# d200_zm1020_rev_b.net
KiCad netlist of a schematic drawn in EAGLE
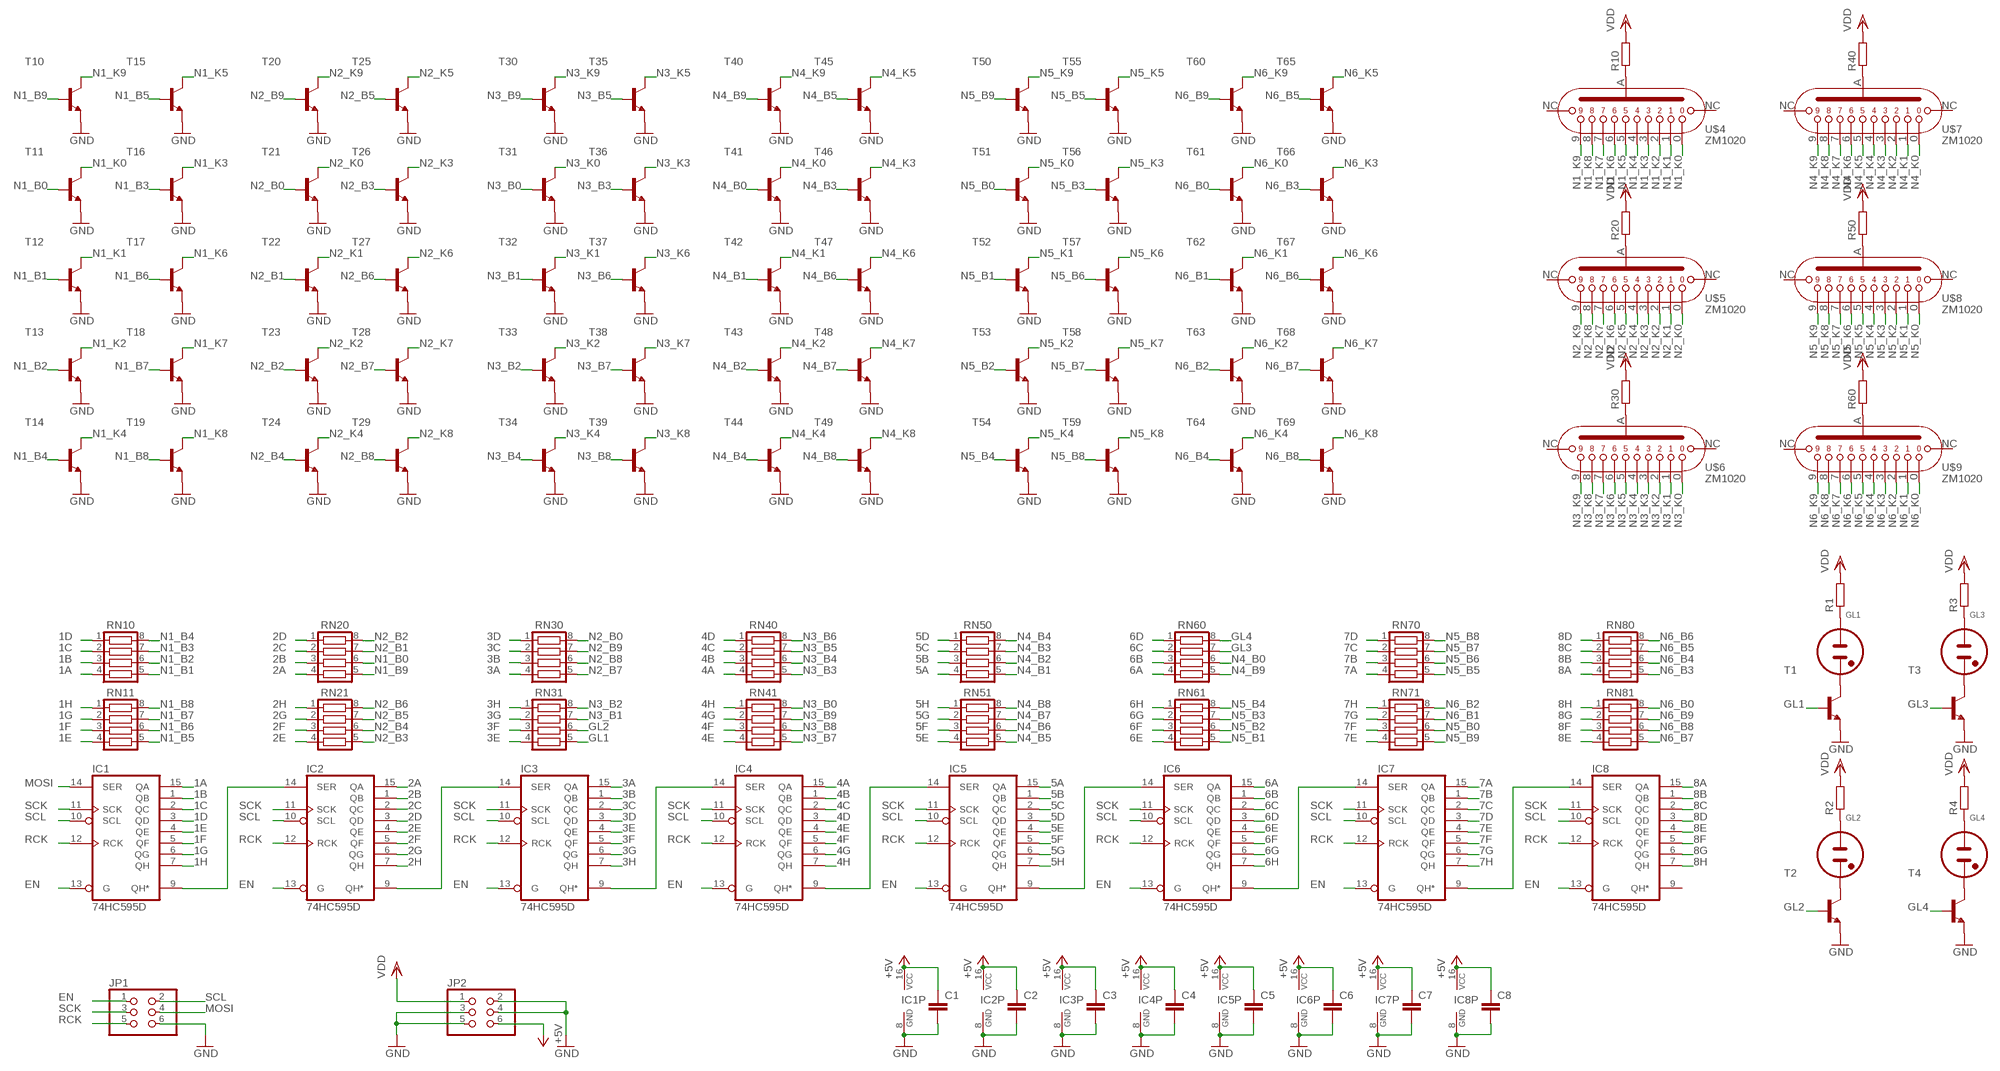
[diagram p0: schematic, sheet 1]

(export (version "E")
  (design (tool "Eeschema 10.0.6"))
  (components
    (comp (ref "C1")
      (value "C-EUC0603")
      (footprint "eagle-import:C0603")
      (libsource (lib "eagle-import") (part "C-EUC0603"))
    )
    (comp (ref "C2")
      (value "C-EUC0603")
      (footprint "eagle-import:C0603")
      (libsource (lib "eagle-import") (part "C-EUC0603"))
    )
    (comp (ref "C3")
      (value "C-EUC0603")
      (footprint "eagle-import:C0603")
      (libsource (lib "eagle-import") (part "C-EUC0603"))
    )
    (comp (ref "C4")
      (value "C-EUC0603")
      (footprint "eagle-import:C0603")
      (libsource (lib "eagle-import") (part "C-EUC0603"))
    )
    (comp (ref "C5")
      (value "C-EUC0603")
      (footprint "eagle-import:C0603")
      (libsource (lib "eagle-import") (part "C-EUC0603"))
    )
    (comp (ref "C6")
      (value "C-EUC0603")
      (footprint "eagle-import:C0603")
      (libsource (lib "eagle-import") (part "C-EUC0603"))
    )
    (comp (ref "C7")
      (value "C-EUC0603")
      (footprint "eagle-import:C0603")
      (libsource (lib "eagle-import") (part "C-EUC0603"))
    )
    (comp (ref "C8")
      (value "C-EUC0603")
      (footprint "eagle-import:C0603")
      (libsource (lib "eagle-import") (part "C-EUC0603"))
    )
    (comp (ref "GL1")
      (value "NE2-NEON-BULB-DRILL")
      (footprint "eagle-import:NE2-NEON-BULB-DRILL")
      (libsource (lib "eagle-import") (part "NE2-NEON-BULB-DRILL"))
    )
    (comp (ref "GL2")
      (value "NE2-NEON-BULB-DRILL")
      (footprint "eagle-import:NE2-NEON-BULB-DRILL")
      (libsource (lib "eagle-import") (part "NE2-NEON-BULB-DRILL"))
    )
    (comp (ref "GL3")
      (value "NE2-NEON-BULB-DRILL")
      (footprint "eagle-import:NE2-NEON-BULB-DRILL")
      (libsource (lib "eagle-import") (part "NE2-NEON-BULB-DRILL"))
    )
    (comp (ref "GL4")
      (value "NE2-NEON-BULB-DRILL")
      (footprint "eagle-import:NE2-NEON-BULB-DRILL")
      (libsource (lib "eagle-import") (part "NE2-NEON-BULB-DRILL"))
    )
    (comp (ref "IC1")
      (value "74HC595D")
      (footprint "eagle-import:SO16")
      (libsource (lib "eagle-import") (part "74595DHC"))
    )
    (comp (ref "IC2")
      (value "74HC595D")
      (footprint "eagle-import:SO16")
      (libsource (lib "eagle-import") (part "74595DHC"))
    )
    (comp (ref "IC3")
      (value "74HC595D")
      (footprint "eagle-import:SO16")
      (libsource (lib "eagle-import") (part "74595DHC"))
    )
    (comp (ref "IC4")
      (value "74HC595D")
      (footprint "eagle-import:SO16")
      (libsource (lib "eagle-import") (part "74595DHC"))
    )
    (comp (ref "IC5")
      (value "74HC595D")
      (footprint "eagle-import:SO16")
      (libsource (lib "eagle-import") (part "74595DHC"))
    )
    (comp (ref "IC6")
      (value "74HC595D")
      (footprint "eagle-import:SO16")
      (libsource (lib "eagle-import") (part "74595DHC"))
    )
    (comp (ref "IC7")
      (value "74HC595D")
      (footprint "eagle-import:SO16")
      (libsource (lib "eagle-import") (part "74595DHC"))
    )
    (comp (ref "IC8")
      (value "74HC595D")
      (footprint "eagle-import:SO16")
      (libsource (lib "eagle-import") (part "74595DHC"))
    )
    (comp (ref "JP1")
      (value "PINHD-2X3_2.54-SMD")
      (footprint "eagle-import:2X03SMD")
      (libsource (lib "eagle-import") (part "PINHD-2X3_2.54-SMD"))
    )
    (comp (ref "JP2")
      (value "PINHD-2X3_2.54-SMD")
      (footprint "eagle-import:2X03SMD")
      (libsource (lib "eagle-import") (part "PINHD-2X3_2.54-SMD"))
    )
    (comp (ref "R1")
      (value "R-EU_R0603")
      (footprint "eagle-import:R0603")
      (libsource (lib "eagle-import") (part "R-EU_R0603"))
    )
    (comp (ref "R2")
      (value "R-EU_R0603")
      (footprint "eagle-import:R0603")
      (libsource (lib "eagle-import") (part "R-EU_R0603"))
    )
    (comp (ref "R3")
      (value "R-EU_R0603")
      (footprint "eagle-import:R0603")
      (libsource (lib "eagle-import") (part "R-EU_R0603"))
    )
    (comp (ref "R4")
      (value "R-EU_R0603")
      (footprint "eagle-import:R0603")
      (libsource (lib "eagle-import") (part "R-EU_R0603"))
    )
    (comp (ref "R10")
      (value "R-EU_R0603")
      (footprint "eagle-import:R0603")
      (libsource (lib "eagle-import") (part "R-EU_R0603"))
    )
    (comp (ref "R20")
      (value "R-EU_R0603")
      (footprint "eagle-import:R0603")
      (libsource (lib "eagle-import") (part "R-EU_R0603"))
    )
    (comp (ref "R30")
      (value "R-EU_R0603")
      (footprint "eagle-import:R0603")
      (libsource (lib "eagle-import") (part "R-EU_R0603"))
    )
    (comp (ref "R40")
      (value "R-EU_R0603")
      (footprint "eagle-import:R0603")
      (libsource (lib "eagle-import") (part "R-EU_R0603"))
    )
    (comp (ref "R50")
      (value "R-EU_R0603")
      (footprint "eagle-import:R0603")
      (libsource (lib "eagle-import") (part "R-EU_R0603"))
    )
    (comp (ref "R60")
      (value "R-EU_R0603")
      (footprint "eagle-import:R0603")
      (libsource (lib "eagle-import") (part "R-EU_R0603"))
    )
    (comp (ref "RN10")
      (value "CTS742C083")
      (footprint "eagle-import:CTS742C083")
      (fields (field (name "OC_FARNELL") "unknown") (field (name "OC_NEWARK") "unknown"))
      (libsource (lib "eagle-import") (part "CTS742C083"))
    )
    (comp (ref "RN11")
      (value "CTS742C083")
      (footprint "eagle-import:CTS742C083")
      (fields (field (name "OC_FARNELL") "unknown") (field (name "OC_NEWARK") "unknown"))
      (libsource (lib "eagle-import") (part "CTS742C083"))
    )
    (comp (ref "RN20")
      (value "CTS742C083")
      (footprint "eagle-import:CTS742C083")
      (fields (field (name "OC_FARNELL") "unknown") (field (name "OC_NEWARK") "unknown"))
      (libsource (lib "eagle-import") (part "CTS742C083"))
    )
    (comp (ref "RN21")
      (value "CTS742C083")
      (footprint "eagle-import:CTS742C083")
      (fields (field (name "OC_FARNELL") "unknown") (field (name "OC_NEWARK") "unknown"))
      (libsource (lib "eagle-import") (part "CTS742C083"))
    )
    (comp (ref "RN30")
      (value "CTS742C083")
      (footprint "eagle-import:CTS742C083")
      (fields (field (name "OC_FARNELL") "unknown") (field (name "OC_NEWARK") "unknown"))
      (libsource (lib "eagle-import") (part "CTS742C083"))
    )
    (comp (ref "RN31")
      (value "CTS742C083")
      (footprint "eagle-import:CTS742C083")
      (fields (field (name "OC_FARNELL") "unknown") (field (name "OC_NEWARK") "unknown"))
      (libsource (lib "eagle-import") (part "CTS742C083"))
    )
    (comp (ref "RN40")
      (value "CTS742C083")
      (footprint "eagle-import:CTS742C083")
      (fields (field (name "OC_FARNELL") "unknown") (field (name "OC_NEWARK") "unknown"))
      (libsource (lib "eagle-import") (part "CTS742C083"))
    )
    (comp (ref "RN41")
      (value "CTS742C083")
      (footprint "eagle-import:CTS742C083")
      (fields (field (name "OC_FARNELL") "unknown") (field (name "OC_NEWARK") "unknown"))
      (libsource (lib "eagle-import") (part "CTS742C083"))
    )
    (comp (ref "RN50")
      (value "CTS742C083")
      (footprint "eagle-import:CTS742C083")
      (fields (field (name "OC_FARNELL") "unknown") (field (name "OC_NEWARK") "unknown"))
      (libsource (lib "eagle-import") (part "CTS742C083"))
    )
    (comp (ref "RN51")
      (value "CTS742C083")
      (footprint "eagle-import:CTS742C083")
      (fields (field (name "OC_FARNELL") "unknown") (field (name "OC_NEWARK") "unknown"))
      (libsource (lib "eagle-import") (part "CTS742C083"))
    )
    (comp (ref "RN60")
      (value "CTS742C083")
      (footprint "eagle-import:CTS742C083")
      (fields (field (name "OC_FARNELL") "unknown") (field (name "OC_NEWARK") "unknown"))
      (libsource (lib "eagle-import") (part "CTS742C083"))
    )
    (comp (ref "RN61")
      (value "CTS742C083")
      (footprint "eagle-import:CTS742C083")
      (fields (field (name "OC_FARNELL") "unknown") (field (name "OC_NEWARK") "unknown"))
      (libsource (lib "eagle-import") (part "CTS742C083"))
    )
    (comp (ref "RN70")
      (value "CTS742C083")
      (footprint "eagle-import:CTS742C083")
      (fields (field (name "OC_FARNELL") "unknown") (field (name "OC_NEWARK") "unknown"))
      (libsource (lib "eagle-import") (part "CTS742C083"))
    )
    (comp (ref "RN71")
      (value "CTS742C083")
      (footprint "eagle-import:CTS742C083")
      (fields (field (name "OC_FARNELL") "unknown") (field (name "OC_NEWARK") "unknown"))
      (libsource (lib "eagle-import") (part "CTS742C083"))
    )
    (comp (ref "RN80")
      (value "CTS742C083")
      (footprint "eagle-import:CTS742C083")
      (fields (field (name "OC_FARNELL") "unknown") (field (name "OC_NEWARK") "unknown"))
      (libsource (lib "eagle-import") (part "CTS742C083"))
    )
    (comp (ref "RN81")
      (value "CTS742C083")
      (footprint "eagle-import:CTS742C083")
      (fields (field (name "OC_FARNELL") "unknown") (field (name "OC_NEWARK") "unknown"))
      (libsource (lib "eagle-import") (part "CTS742C083"))
    )
    (comp (ref "T1")
      (value "SMBTA42")
      (footprint "eagle-import:SOT23")
      (libsource (lib "eagle-import") (part "SMBTA42"))
    )
    (comp (ref "T2")
      (value "SMBTA42")
      (footprint "eagle-import:SOT23")
      (libsource (lib "eagle-import") (part "SMBTA42"))
    )
    (comp (ref "T3")
      (value "SMBTA42")
      (footprint "eagle-import:SOT23")
      (libsource (lib "eagle-import") (part "SMBTA42"))
    )
    (comp (ref "T4")
      (value "SMBTA42")
      (footprint "eagle-import:SOT23")
      (libsource (lib "eagle-import") (part "SMBTA42"))
    )
    (comp (ref "T10")
      (value "SMBTA42")
      (footprint "eagle-import:SOT23")
      (libsource (lib "eagle-import") (part "SMBTA42"))
    )
    (comp (ref "T11")
      (value "SMBTA42")
      (footprint "eagle-import:SOT23")
      (libsource (lib "eagle-import") (part "SMBTA42"))
    )
    (comp (ref "T12")
      (value "SMBTA42")
      (footprint "eagle-import:SOT23")
      (libsource (lib "eagle-import") (part "SMBTA42"))
    )
    (comp (ref "T13")
      (value "SMBTA42")
      (footprint "eagle-import:SOT23")
      (libsource (lib "eagle-import") (part "SMBTA42"))
    )
    (comp (ref "T14")
      (value "SMBTA42")
      (footprint "eagle-import:SOT23")
      (libsource (lib "eagle-import") (part "SMBTA42"))
    )
    (comp (ref "T15")
      (value "SMBTA42")
      (footprint "eagle-import:SOT23")
      (libsource (lib "eagle-import") (part "SMBTA42"))
    )
    (comp (ref "T16")
      (value "SMBTA42")
      (footprint "eagle-import:SOT23")
      (libsource (lib "eagle-import") (part "SMBTA42"))
    )
    (comp (ref "T17")
      (value "SMBTA42")
      (footprint "eagle-import:SOT23")
      (libsource (lib "eagle-import") (part "SMBTA42"))
    )
    (comp (ref "T18")
      (value "SMBTA42")
      (footprint "eagle-import:SOT23")
      (libsource (lib "eagle-import") (part "SMBTA42"))
    )
    (comp (ref "T19")
      (value "SMBTA42")
      (footprint "eagle-import:SOT23")
      (libsource (lib "eagle-import") (part "SMBTA42"))
    )
    (comp (ref "T20")
      (value "SMBTA42")
      (footprint "eagle-import:SOT23")
      (libsource (lib "eagle-import") (part "SMBTA42"))
    )
    (comp (ref "T21")
      (value "SMBTA42")
      (footprint "eagle-import:SOT23")
      (libsource (lib "eagle-import") (part "SMBTA42"))
    )
    (comp (ref "T22")
      (value "SMBTA42")
      (footprint "eagle-import:SOT23")
      (libsource (lib "eagle-import") (part "SMBTA42"))
    )
    (comp (ref "T23")
      (value "SMBTA42")
      (footprint "eagle-import:SOT23")
      (libsource (lib "eagle-import") (part "SMBTA42"))
    )
    (comp (ref "T24")
      (value "SMBTA42")
      (footprint "eagle-import:SOT23")
      (libsource (lib "eagle-import") (part "SMBTA42"))
    )
    (comp (ref "T25")
      (value "SMBTA42")
      (footprint "eagle-import:SOT23")
      (libsource (lib "eagle-import") (part "SMBTA42"))
    )
    (comp (ref "T26")
      (value "SMBTA42")
      (footprint "eagle-import:SOT23")
      (libsource (lib "eagle-import") (part "SMBTA42"))
    )
    (comp (ref "T27")
      (value "SMBTA42")
      (footprint "eagle-import:SOT23")
      (libsource (lib "eagle-import") (part "SMBTA42"))
    )
    (comp (ref "T28")
      (value "SMBTA42")
      (footprint "eagle-import:SOT23")
      (libsource (lib "eagle-import") (part "SMBTA42"))
    )
    (comp (ref "T29")
      (value "SMBTA42")
      (footprint "eagle-import:SOT23")
      (libsource (lib "eagle-import") (part "SMBTA42"))
    )
    (comp (ref "T30")
      (value "SMBTA42")
      (footprint "eagle-import:SOT23")
      (libsource (lib "eagle-import") (part "SMBTA42"))
    )
    (comp (ref "T31")
      (value "SMBTA42")
      (footprint "eagle-import:SOT23")
      (libsource (lib "eagle-import") (part "SMBTA42"))
    )
    (comp (ref "T32")
      (value "SMBTA42")
      (footprint "eagle-import:SOT23")
      (libsource (lib "eagle-import") (part "SMBTA42"))
    )
    (comp (ref "T33")
      (value "SMBTA42")
      (footprint "eagle-import:SOT23")
      (libsource (lib "eagle-import") (part "SMBTA42"))
    )
    (comp (ref "T34")
      (value "SMBTA42")
      (footprint "eagle-import:SOT23")
      (libsource (lib "eagle-import") (part "SMBTA42"))
    )
    (comp (ref "T35")
      (value "SMBTA42")
      (footprint "eagle-import:SOT23")
      (libsource (lib "eagle-import") (part "SMBTA42"))
    )
    (comp (ref "T36")
      (value "SMBTA42")
      (footprint "eagle-import:SOT23")
      (libsource (lib "eagle-import") (part "SMBTA42"))
    )
    (comp (ref "T37")
      (value "SMBTA42")
      (footprint "eagle-import:SOT23")
      (libsource (lib "eagle-import") (part "SMBTA42"))
    )
    (comp (ref "T38")
      (value "SMBTA42")
      (footprint "eagle-import:SOT23")
      (libsource (lib "eagle-import") (part "SMBTA42"))
    )
    (comp (ref "T39")
      (value "SMBTA42")
      (footprint "eagle-import:SOT23")
      (libsource (lib "eagle-import") (part "SMBTA42"))
    )
    (comp (ref "T40")
      (value "SMBTA42")
      (footprint "eagle-import:SOT23")
      (libsource (lib "eagle-import") (part "SMBTA42"))
    )
    (comp (ref "T41")
      (value "SMBTA42")
      (footprint "eagle-import:SOT23")
      (libsource (lib "eagle-import") (part "SMBTA42"))
    )
    (comp (ref "T42")
      (value "SMBTA42")
      (footprint "eagle-import:SOT23")
      (libsource (lib "eagle-import") (part "SMBTA42"))
    )
    (comp (ref "T43")
      (value "SMBTA42")
      (footprint "eagle-import:SOT23")
      (libsource (lib "eagle-import") (part "SMBTA42"))
    )
    (comp (ref "T44")
      (value "SMBTA42")
      (footprint "eagle-import:SOT23")
      (libsource (lib "eagle-import") (part "SMBTA42"))
    )
    (comp (ref "T45")
      (value "SMBTA42")
      (footprint "eagle-import:SOT23")
      (libsource (lib "eagle-import") (part "SMBTA42"))
    )
    (comp (ref "T46")
      (value "SMBTA42")
      (footprint "eagle-import:SOT23")
      (libsource (lib "eagle-import") (part "SMBTA42"))
    )
    (comp (ref "T47")
      (value "SMBTA42")
      (footprint "eagle-import:SOT23")
      (libsource (lib "eagle-import") (part "SMBTA42"))
    )
    (comp (ref "T48")
      (value "SMBTA42")
      (footprint "eagle-import:SOT23")
      (libsource (lib "eagle-import") (part "SMBTA42"))
    )
    (comp (ref "T49")
      (value "SMBTA42")
      (footprint "eagle-import:SOT23")
      (libsource (lib "eagle-import") (part "SMBTA42"))
    )
    (comp (ref "T50")
      (value "SMBTA42")
      (footprint "eagle-import:SOT23")
      (libsource (lib "eagle-import") (part "SMBTA42"))
    )
    (comp (ref "T51")
      (value "SMBTA42")
      (footprint "eagle-import:SOT23")
      (libsource (lib "eagle-import") (part "SMBTA42"))
    )
    (comp (ref "T52")
      (value "SMBTA42")
      (footprint "eagle-import:SOT23")
      (libsource (lib "eagle-import") (part "SMBTA42"))
    )
    (comp (ref "T53")
      (value "SMBTA42")
      (footprint "eagle-import:SOT23")
      (libsource (lib "eagle-import") (part "SMBTA42"))
    )
    (comp (ref "T54")
      (value "SMBTA42")
      (footprint "eagle-import:SOT23")
      (libsource (lib "eagle-import") (part "SMBTA42"))
    )
    (comp (ref "T55")
      (value "SMBTA42")
      (footprint "eagle-import:SOT23")
      (libsource (lib "eagle-import") (part "SMBTA42"))
    )
    (comp (ref "T56")
      (value "SMBTA42")
      (footprint "eagle-import:SOT23")
      (libsource (lib "eagle-import") (part "SMBTA42"))
    )
    (comp (ref "T57")
      (value "SMBTA42")
      (footprint "eagle-import:SOT23")
      (libsource (lib "eagle-import") (part "SMBTA42"))
    )
    (comp (ref "T58")
      (value "SMBTA42")
      (footprint "eagle-import:SOT23")
      (libsource (lib "eagle-import") (part "SMBTA42"))
    )
    (comp (ref "T59")
      (value "SMBTA42")
      (footprint "eagle-import:SOT23")
      (libsource (lib "eagle-import") (part "SMBTA42"))
    )
    (comp (ref "T60")
      (value "SMBTA42")
      (footprint "eagle-import:SOT23")
      (libsource (lib "eagle-import") (part "SMBTA42"))
    )
    (comp (ref "T61")
      (value "SMBTA42")
      (footprint "eagle-import:SOT23")
      (libsource (lib "eagle-import") (part "SMBTA42"))
    )
    (comp (ref "T62")
      (value "SMBTA42")
      (footprint "eagle-import:SOT23")
      (libsource (lib "eagle-import") (part "SMBTA42"))
    )
    (comp (ref "T63")
      (value "SMBTA42")
      (footprint "eagle-import:SOT23")
      (libsource (lib "eagle-import") (part "SMBTA42"))
    )
    (comp (ref "T64")
      (value "SMBTA42")
      (footprint "eagle-import:SOT23")
      (libsource (lib "eagle-import") (part "SMBTA42"))
    )
    (comp (ref "T65")
      (value "SMBTA42")
      (footprint "eagle-import:SOT23")
      (libsource (lib "eagle-import") (part "SMBTA42"))
    )
    (comp (ref "T66")
      (value "SMBTA42")
      (footprint "eagle-import:SOT23")
      (libsource (lib "eagle-import") (part "SMBTA42"))
    )
    (comp (ref "T67")
      (value "SMBTA42")
      (footprint "eagle-import:SOT23")
      (libsource (lib "eagle-import") (part "SMBTA42"))
    )
    (comp (ref "T68")
      (value "SMBTA42")
      (footprint "eagle-import:SOT23")
      (libsource (lib "eagle-import") (part "SMBTA42"))
    )
    (comp (ref "T69")
      (value "SMBTA42")
      (footprint "eagle-import:SOT23")
      (libsource (lib "eagle-import") (part "SMBTA42"))
    )
    (comp (ref "U$4")
      (value "ZM1020")
      (footprint "eagle-import:ZM1020")
      (libsource (lib "eagle-import") (part "ZM1020"))
    )
    (comp (ref "U$5")
      (value "ZM1020")
      (footprint "eagle-import:ZM1020")
      (libsource (lib "eagle-import") (part "ZM1020"))
    )
    (comp (ref "U$6")
      (value "ZM1020")
      (footprint "eagle-import:ZM1020")
      (libsource (lib "eagle-import") (part "ZM1020"))
    )
    (comp (ref "U$7")
      (value "ZM1020")
      (footprint "eagle-import:ZM1020")
      (libsource (lib "eagle-import") (part "ZM1020"))
    )
    (comp (ref "U$8")
      (value "ZM1020")
      (footprint "eagle-import:ZM1020")
      (libsource (lib "eagle-import") (part "ZM1020"))
    )
    (comp (ref "U$9")
      (value "ZM1020")
      (footprint "eagle-import:ZM1020")
      (libsource (lib "eagle-import") (part "ZM1020"))
    )
  )
  (nets
    (net (code "1") (name "+5V") (class "Default")
      (node (ref "C1") (pin "1") (pinfunction "1_1") (pintype "passive"))
      (node (ref "C2") (pin "1") (pinfunction "1_1") (pintype "passive"))
      (node (ref "C3") (pin "1") (pinfunction "1_1") (pintype "passive"))
      (node (ref "C4") (pin "1") (pinfunction "1_1") (pintype "passive"))
      (node (ref "C5") (pin "1") (pinfunction "1_1") (pintype "passive"))
      (node (ref "C6") (pin "1") (pinfunction "1_1") (pintype "passive"))
      (node (ref "C7") (pin "1") (pinfunction "1_1") (pintype "passive"))
      (node (ref "C8") (pin "1") (pinfunction "1_1") (pintype "passive"))
      (node (ref "IC1") (pin "16") (pinfunction "VCC_16") (pintype "power_in"))
      (node (ref "IC2") (pin "16") (pinfunction "VCC_16") (pintype "power_in"))
      (node (ref "IC3") (pin "16") (pinfunction "VCC_16") (pintype "power_in"))
      (node (ref "IC4") (pin "16") (pinfunction "VCC_16") (pintype "power_in"))
      (node (ref "IC5") (pin "16") (pinfunction "VCC_16") (pintype "power_in"))
      (node (ref "IC6") (pin "16") (pinfunction "VCC_16") (pintype "power_in"))
      (node (ref "IC7") (pin "16") (pinfunction "VCC_16") (pintype "power_in"))
      (node (ref "IC8") (pin "16") (pinfunction "VCC_16") (pintype "power_in"))
      (node (ref "JP2") (pin "6") (pinfunction "6_6") (pintype "passive"))
    )
    (net (code "2") (name "/1A") (class "Default")
      (node (ref "IC1") (pin "15") (pinfunction "QA_15") (pintype "tri_state"))
      (node (ref "RN10") (pin "4") (pinfunction "4_4") (pintype "passive"))
    )
    (net (code "3") (name "/1B") (class "Default")
      (node (ref "IC1") (pin "1") (pinfunction "QB_1") (pintype "tri_state"))
      (node (ref "RN10") (pin "3") (pinfunction "3_3") (pintype "passive"))
    )
    (net (code "4") (name "/1C") (class "Default")
      (node (ref "IC1") (pin "2") (pinfunction "QC_2") (pintype "tri_state"))
      (node (ref "RN10") (pin "2") (pinfunction "2_2") (pintype "passive"))
    )
    (net (code "5") (name "/1D") (class "Default")
      (node (ref "IC1") (pin "3") (pinfunction "QD_3") (pintype "tri_state"))
      (node (ref "RN10") (pin "1") (pinfunction "1_1") (pintype "passive"))
    )
    (net (code "6") (name "/1E") (class "Default")
      (node (ref "IC1") (pin "4") (pinfunction "QE_4") (pintype "tri_state"))
      (node (ref "RN11") (pin "4") (pinfunction "4_4") (pintype "passive"))
    )
    (net (code "7") (name "/1F") (class "Default")
      (node (ref "IC1") (pin "5") (pinfunction "QF_5") (pintype "tri_state"))
      (node (ref "RN11") (pin "3") (pinfunction "3_3") (pintype "passive"))
    )
    (net (code "8") (name "/1G") (class "Default")
      (node (ref "IC1") (pin "6") (pinfunction "QG_6") (pintype "tri_state"))
      (node (ref "RN11") (pin "2") (pinfunction "2_2") (pintype "passive"))
    )
    (net (code "9") (name "/1H") (class "Default")
      (node (ref "IC1") (pin "7") (pinfunction "QH_7") (pintype "tri_state"))
      (node (ref "RN11") (pin "1") (pinfunction "1_1") (pintype "passive"))
    )
    (net (code "10") (name "/2A") (class "Default")
      (node (ref "IC2") (pin "15") (pinfunction "QA_15") (pintype "tri_state"))
      (node (ref "RN20") (pin "4") (pinfunction "4_4") (pintype "passive"))
    )
    (net (code "11") (name "/2B") (class "Default")
      (node (ref "IC2") (pin "1") (pinfunction "QB_1") (pintype "tri_state"))
      (node (ref "RN20") (pin "3") (pinfunction "3_3") (pintype "passive"))
    )
    (net (code "12") (name "/2C") (class "Default")
      (node (ref "IC2") (pin "2") (pinfunction "QC_2") (pintype "tri_state"))
      (node (ref "RN20") (pin "2") (pinfunction "2_2") (pintype "passive"))
    )
    (net (code "13") (name "/2D") (class "Default")
      (node (ref "IC2") (pin "3") (pinfunction "QD_3") (pintype "tri_state"))
      (node (ref "RN20") (pin "1") (pinfunction "1_1") (pintype "passive"))
    )
    (net (code "14") (name "/2E") (class "Default")
      (node (ref "IC2") (pin "4") (pinfunction "QE_4") (pintype "tri_state"))
      (node (ref "RN21") (pin "4") (pinfunction "4_4") (pintype "passive"))
    )
    (net (code "15") (name "/2F") (class "Default")
      (node (ref "IC2") (pin "5") (pinfunction "QF_5") (pintype "tri_state"))
      (node (ref "RN21") (pin "3") (pinfunction "3_3") (pintype "passive"))
    )
    (net (code "16") (name "/2G") (class "Default")
      (node (ref "IC2") (pin "6") (pinfunction "QG_6") (pintype "tri_state"))
      (node (ref "RN21") (pin "2") (pinfunction "2_2") (pintype "passive"))
    )
    (net (code "17") (name "/2H") (class "Default")
      (node (ref "IC2") (pin "7") (pinfunction "QH_7") (pintype "tri_state"))
      (node (ref "RN21") (pin "1") (pinfunction "1_1") (pintype "passive"))
    )
    (net (code "18") (name "/3A") (class "Default")
      (node (ref "IC3") (pin "15") (pinfunction "QA_15") (pintype "tri_state"))
      (node (ref "RN30") (pin "4") (pinfunction "4_4") (pintype "passive"))
    )
    (net (code "19") (name "/3B") (class "Default")
      (node (ref "IC3") (pin "1") (pinfunction "QB_1") (pintype "tri_state"))
      (node (ref "RN30") (pin "3") (pinfunction "3_3") (pintype "passive"))
    )
    (net (code "20") (name "/3C") (class "Default")
      (node (ref "IC3") (pin "2") (pinfunction "QC_2") (pintype "tri_state"))
      (node (ref "RN30") (pin "2") (pinfunction "2_2") (pintype "passive"))
    )
    (net (code "21") (name "/3D") (class "Default")
      (node (ref "IC3") (pin "3") (pinfunction "QD_3") (pintype "tri_state"))
      (node (ref "RN30") (pin "1") (pinfunction "1_1") (pintype "passive"))
    )
    (net (code "22") (name "/3E") (class "Default")
      (node (ref "IC3") (pin "4") (pinfunction "QE_4") (pintype "tri_state"))
      (node (ref "RN31") (pin "4") (pinfunction "4_4") (pintype "passive"))
    )
    (net (code "23") (name "/3F") (class "Default")
      (node (ref "IC3") (pin "5") (pinfunction "QF_5") (pintype "tri_state"))
      (node (ref "RN31") (pin "3") (pinfunction "3_3") (pintype "passive"))
    )
    (net (code "24") (name "/3G") (class "Default")
      (node (ref "IC3") (pin "6") (pinfunction "QG_6") (pintype "tri_state"))
      (node (ref "RN31") (pin "2") (pinfunction "2_2") (pintype "passive"))
    )
    (net (code "25") (name "/3H") (class "Default")
      (node (ref "IC3") (pin "7") (pinfunction "QH_7") (pintype "tri_state"))
      (node (ref "RN31") (pin "1") (pinfunction "1_1") (pintype "passive"))
    )
    (net (code "26") (name "/4A") (class "Default")
      (node (ref "IC4") (pin "15") (pinfunction "QA_15") (pintype "tri_state"))
      (node (ref "RN40") (pin "4") (pinfunction "4_4") (pintype "passive"))
    )
    (net (code "27") (name "/4B") (class "Default")
      (node (ref "IC4") (pin "1") (pinfunction "QB_1") (pintype "tri_state"))
      (node (ref "RN40") (pin "3") (pinfunction "3_3") (pintype "passive"))
    )
    (net (code "28") (name "/4C") (class "Default")
      (node (ref "IC4") (pin "2") (pinfunction "QC_2") (pintype "tri_state"))
      (node (ref "RN40") (pin "2") (pinfunction "2_2") (pintype "passive"))
    )
    (net (code "29") (name "/4D") (class "Default")
      (node (ref "IC4") (pin "3") (pinfunction "QD_3") (pintype "tri_state"))
      (node (ref "RN40") (pin "1") (pinfunction "1_1") (pintype "passive"))
    )
    (net (code "30") (name "/4E") (class "Default")
      (node (ref "IC4") (pin "4") (pinfunction "QE_4") (pintype "tri_state"))
      (node (ref "RN41") (pin "4") (pinfunction "4_4") (pintype "passive"))
    )
    (net (code "31") (name "/4F") (class "Default")
      (node (ref "IC4") (pin "5") (pinfunction "QF_5") (pintype "tri_state"))
      (node (ref "RN41") (pin "3") (pinfunction "3_3") (pintype "passive"))
    )
    (net (code "32") (name "/4G") (class "Default")
      (node (ref "IC4") (pin "6") (pinfunction "QG_6") (pintype "tri_state"))
      (node (ref "RN41") (pin "2") (pinfunction "2_2") (pintype "passive"))
    )
    (net (code "33") (name "/4H") (class "Default")
      (node (ref "IC4") (pin "7") (pinfunction "QH_7") (pintype "tri_state"))
      (node (ref "RN41") (pin "1") (pinfunction "1_1") (pintype "passive"))
    )
    (net (code "34") (name "/5A") (class "Default")
      (node (ref "IC5") (pin "15") (pinfunction "QA_15") (pintype "tri_state"))
      (node (ref "RN50") (pin "4") (pinfunction "4_4") (pintype "passive"))
    )
    (net (code "35") (name "/5B") (class "Default")
      (node (ref "IC5") (pin "1") (pinfunction "QB_1") (pintype "tri_state"))
      (node (ref "RN50") (pin "3") (pinfunction "3_3") (pintype "passive"))
    )
    (net (code "36") (name "/5C") (class "Default")
      (node (ref "IC5") (pin "2") (pinfunction "QC_2") (pintype "tri_state"))
      (node (ref "RN50") (pin "2") (pinfunction "2_2") (pintype "passive"))
    )
    (net (code "37") (name "/5D") (class "Default")
      (node (ref "IC5") (pin "3") (pinfunction "QD_3") (pintype "tri_state"))
      (node (ref "RN50") (pin "1") (pinfunction "1_1") (pintype "passive"))
    )
    (net (code "38") (name "/5E") (class "Default")
      (node (ref "IC5") (pin "4") (pinfunction "QE_4") (pintype "tri_state"))
      (node (ref "RN51") (pin "4") (pinfunction "4_4") (pintype "passive"))
    )
    (net (code "39") (name "/5F") (class "Default")
      (node (ref "IC5") (pin "5") (pinfunction "QF_5") (pintype "tri_state"))
      (node (ref "RN51") (pin "3") (pinfunction "3_3") (pintype "passive"))
    )
    (net (code "40") (name "/5G") (class "Default")
      (node (ref "IC5") (pin "6") (pinfunction "QG_6") (pintype "tri_state"))
      (node (ref "RN51") (pin "2") (pinfunction "2_2") (pintype "passive"))
    )
    (net (code "41") (name "/5H") (class "Default")
      (node (ref "IC5") (pin "7") (pinfunction "QH_7") (pintype "tri_state"))
      (node (ref "RN51") (pin "1") (pinfunction "1_1") (pintype "passive"))
    )
    (net (code "42") (name "/6A") (class "Default")
      (node (ref "IC6") (pin "15") (pinfunction "QA_15") (pintype "tri_state"))
      (node (ref "RN60") (pin "4") (pinfunction "4_4") (pintype "passive"))
    )
    (net (code "43") (name "/6B") (class "Default")
      (node (ref "IC6") (pin "1") (pinfunction "QB_1") (pintype "tri_state"))
      (node (ref "RN60") (pin "3") (pinfunction "3_3") (pintype "passive"))
    )
    (net (code "44") (name "/6C") (class "Default")
      (node (ref "IC6") (pin "2") (pinfunction "QC_2") (pintype "tri_state"))
      (node (ref "RN60") (pin "2") (pinfunction "2_2") (pintype "passive"))
    )
    (net (code "45") (name "/6D") (class "Default")
      (node (ref "IC6") (pin "3") (pinfunction "QD_3") (pintype "tri_state"))
      (node (ref "RN60") (pin "1") (pinfunction "1_1") (pintype "passive"))
    )
    (net (code "46") (name "/6E") (class "Default")
      (node (ref "IC6") (pin "4") (pinfunction "QE_4") (pintype "tri_state"))
      (node (ref "RN61") (pin "4") (pinfunction "4_4") (pintype "passive"))
    )
    (net (code "47") (name "/6F") (class "Default")
      (node (ref "IC6") (pin "5") (pinfunction "QF_5") (pintype "tri_state"))
      (node (ref "RN61") (pin "3") (pinfunction "3_3") (pintype "passive"))
    )
    (net (code "48") (name "/6G") (class "Default")
      (node (ref "IC6") (pin "6") (pinfunction "QG_6") (pintype "tri_state"))
      (node (ref "RN61") (pin "2") (pinfunction "2_2") (pintype "passive"))
    )
    (net (code "49") (name "/6H") (class "Default")
      (node (ref "IC6") (pin "7") (pinfunction "QH_7") (pintype "tri_state"))
      (node (ref "RN61") (pin "1") (pinfunction "1_1") (pintype "passive"))
    )
    (net (code "50") (name "/7A") (class "Default")
      (node (ref "IC7") (pin "15") (pinfunction "QA_15") (pintype "tri_state"))
      (node (ref "RN70") (pin "4") (pinfunction "4_4") (pintype "passive"))
    )
    (net (code "51") (name "/7B") (class "Default")
      (node (ref "IC7") (pin "1") (pinfunction "QB_1") (pintype "tri_state"))
      (node (ref "RN70") (pin "3") (pinfunction "3_3") (pintype "passive"))
    )
    (net (code "52") (name "/7C") (class "Default")
      (node (ref "IC7") (pin "2") (pinfunction "QC_2") (pintype "tri_state"))
      (node (ref "RN70") (pin "2") (pinfunction "2_2") (pintype "passive"))
    )
    (net (code "53") (name "/7D") (class "Default")
      (node (ref "IC7") (pin "3") (pinfunction "QD_3") (pintype "tri_state"))
      (node (ref "RN70") (pin "1") (pinfunction "1_1") (pintype "passive"))
    )
    (net (code "54") (name "/7E") (class "Default")
      (node (ref "IC7") (pin "4") (pinfunction "QE_4") (pintype "tri_state"))
      (node (ref "RN71") (pin "4") (pinfunction "4_4") (pintype "passive"))
    )
    (net (code "55") (name "/7F") (class "Default")
      (node (ref "IC7") (pin "5") (pinfunction "QF_5") (pintype "tri_state"))
      (node (ref "RN71") (pin "3") (pinfunction "3_3") (pintype "passive"))
    )
    (net (code "56") (name "/7G") (class "Default")
      (node (ref "IC7") (pin "6") (pinfunction "QG_6") (pintype "tri_state"))
      (node (ref "RN71") (pin "2") (pinfunction "2_2") (pintype "passive"))
    )
    (net (code "57") (name "/7H") (class "Default")
      (node (ref "IC7") (pin "7") (pinfunction "QH_7") (pintype "tri_state"))
      (node (ref "RN71") (pin "1") (pinfunction "1_1") (pintype "passive"))
    )
    (net (code "58") (name "/8A") (class "Default")
      (node (ref "IC8") (pin "15") (pinfunction "QA_15") (pintype "tri_state"))
      (node (ref "RN80") (pin "4") (pinfunction "4_4") (pintype "passive"))
    )
    (net (code "59") (name "/8B") (class "Default")
      (node (ref "IC8") (pin "1") (pinfunction "QB_1") (pintype "tri_state"))
      (node (ref "RN80") (pin "3") (pinfunction "3_3") (pintype "passive"))
    )
    (net (code "60") (name "/8C") (class "Default")
      (node (ref "IC8") (pin "2") (pinfunction "QC_2") (pintype "tri_state"))
      (node (ref "RN80") (pin "2") (pinfunction "2_2") (pintype "passive"))
    )
    (net (code "61") (name "/8D") (class "Default")
      (node (ref "IC8") (pin "3") (pinfunction "QD_3") (pintype "tri_state"))
      (node (ref "RN80") (pin "1") (pinfunction "1_1") (pintype "passive"))
    )
    (net (code "62") (name "/8E") (class "Default")
      (node (ref "IC8") (pin "4") (pinfunction "QE_4") (pintype "tri_state"))
      (node (ref "RN81") (pin "4") (pinfunction "4_4") (pintype "passive"))
    )
    (net (code "63") (name "/8F") (class "Default")
      (node (ref "IC8") (pin "5") (pinfunction "QF_5") (pintype "tri_state"))
      (node (ref "RN81") (pin "3") (pinfunction "3_3") (pintype "passive"))
    )
    (net (code "64") (name "/8G") (class "Default")
      (node (ref "IC8") (pin "6") (pinfunction "QG_6") (pintype "tri_state"))
      (node (ref "RN81") (pin "2") (pinfunction "2_2") (pintype "passive"))
    )
    (net (code "65") (name "/8H") (class "Default")
      (node (ref "IC8") (pin "7") (pinfunction "QH_7") (pintype "tri_state"))
      (node (ref "RN81") (pin "1") (pinfunction "1_1") (pintype "passive"))
    )
    (net (code "66") (name "/EN") (class "Default")
      (node (ref "IC1") (pin "13") (pinfunction "G_13") (pintype "input"))
      (node (ref "IC2") (pin "13") (pinfunction "G_13") (pintype "input"))
      (node (ref "IC3") (pin "13") (pinfunction "G_13") (pintype "input"))
      (node (ref "IC4") (pin "13") (pinfunction "G_13") (pintype "input"))
      (node (ref "IC5") (pin "13") (pinfunction "G_13") (pintype "input"))
      (node (ref "IC6") (pin "13") (pinfunction "G_13") (pintype "input"))
      (node (ref "IC7") (pin "13") (pinfunction "G_13") (pintype "input"))
      (node (ref "IC8") (pin "13") (pinfunction "G_13") (pintype "input"))
      (node (ref "JP1") (pin "1") (pinfunction "1_1") (pintype "passive"))
    )
    (net (code "67") (name "/GL1") (class "Default")
      (node (ref "RN31") (pin "5") (pinfunction "5_5") (pintype "passive"))
      (node (ref "T1") (pin "1") (pinfunction "B_1") (pintype "passive"))
    )
    (net (code "68") (name "/GL2") (class "Default")
      (node (ref "RN31") (pin "6") (pinfunction "6_6") (pintype "passive"))
      (node (ref "T2") (pin "1") (pinfunction "B_1") (pintype "passive"))
    )
    (net (code "69") (name "/GL3") (class "Default")
      (node (ref "RN60") (pin "7") (pinfunction "7_7") (pintype "passive"))
      (node (ref "T3") (pin "1") (pinfunction "B_1") (pintype "passive"))
    )
    (net (code "70") (name "/GL4") (class "Default")
      (node (ref "RN60") (pin "8") (pinfunction "8_8") (pintype "passive"))
      (node (ref "T4") (pin "1") (pinfunction "B_1") (pintype "passive"))
    )
    (net (code "71") (name "/MOSI") (class "Default")
      (node (ref "IC1") (pin "14") (pinfunction "SER_14") (pintype "input"))
      (node (ref "JP1") (pin "4") (pinfunction "4_4") (pintype "passive"))
    )
    (net (code "72") (name "/N1_B0") (class "Default")
      (node (ref "RN20") (pin "6") (pinfunction "6_6") (pintype "passive"))
      (node (ref "T11") (pin "1") (pinfunction "B_1") (pintype "passive"))
    )
    (net (code "73") (name "/N1_B1") (class "Default")
      (node (ref "RN10") (pin "5") (pinfunction "5_5") (pintype "passive"))
      (node (ref "T12") (pin "1") (pinfunction "B_1") (pintype "passive"))
    )
    (net (code "74") (name "/N1_B2") (class "Default")
      (node (ref "RN10") (pin "6") (pinfunction "6_6") (pintype "passive"))
      (node (ref "T13") (pin "1") (pinfunction "B_1") (pintype "passive"))
    )
    (net (code "75") (name "/N1_B3") (class "Default")
      (node (ref "RN10") (pin "7") (pinfunction "7_7") (pintype "passive"))
      (node (ref "T16") (pin "1") (pinfunction "B_1") (pintype "passive"))
    )
    (net (code "76") (name "/N1_B4") (class "Default")
      (node (ref "RN10") (pin "8") (pinfunction "8_8") (pintype "passive"))
      (node (ref "T14") (pin "1") (pinfunction "B_1") (pintype "passive"))
    )
    (net (code "77") (name "/N1_B5") (class "Default")
      (node (ref "RN11") (pin "5") (pinfunction "5_5") (pintype "passive"))
      (node (ref "T15") (pin "1") (pinfunction "B_1") (pintype "passive"))
    )
    (net (code "78") (name "/N1_B6") (class "Default")
      (node (ref "RN11") (pin "6") (pinfunction "6_6") (pintype "passive"))
      (node (ref "T17") (pin "1") (pinfunction "B_1") (pintype "passive"))
    )
    (net (code "79") (name "/N1_B7") (class "Default")
      (node (ref "RN11") (pin "7") (pinfunction "7_7") (pintype "passive"))
      (node (ref "T18") (pin "1") (pinfunction "B_1") (pintype "passive"))
    )
    (net (code "80") (name "/N1_B8") (class "Default")
      (node (ref "RN11") (pin "8") (pinfunction "8_8") (pintype "passive"))
      (node (ref "T19") (pin "1") (pinfunction "B_1") (pintype "passive"))
    )
    (net (code "81") (name "/N1_B9") (class "Default")
      (node (ref "RN20") (pin "5") (pinfunction "5_5") (pintype "passive"))
      (node (ref "T10") (pin "1") (pinfunction "B_1") (pintype "passive"))
    )
    (net (code "82") (name "/N1_K0") (class "Default")
      (node (ref "T11") (pin "3") (pinfunction "C_3") (pintype "passive"))
      (node (ref "U$4") (pin "P3") (pinfunction "0_P3") (pintype "bidirectional"))
    )
    (net (code "83") (name "/N1_K1") (class "Default")
      (node (ref "T12") (pin "3") (pinfunction "C_3") (pintype "passive"))
      (node (ref "U$4") (pin "P13") (pinfunction "1_P13") (pintype "bidirectional"))
    )
    (net (code "84") (name "/N1_K2") (class "Default")
      (node (ref "T13") (pin "3") (pinfunction "C_3") (pintype "passive"))
      (node (ref "U$4") (pin "P12") (pinfunction "2_P12") (pintype "bidirectional"))
    )
    (net (code "85") (name "/N1_K3") (class "Default")
      (node (ref "T16") (pin "3") (pinfunction "C_3") (pintype "passive"))
      (node (ref "U$4") (pin "P11") (pinfunction "3_P11") (pintype "bidirectional"))
    )
    (net (code "86") (name "/N1_K4") (class "Default")
      (node (ref "T14") (pin "3") (pinfunction "C_3") (pintype "passive"))
      (node (ref "U$4") (pin "P10") (pinfunction "4_P10") (pintype "bidirectional"))
    )
    (net (code "87") (name "/N1_K5") (class "Default")
      (node (ref "T15") (pin "3") (pinfunction "C_3") (pintype "passive"))
      (node (ref "U$4") (pin "P9") (pinfunction "5_P9") (pintype "bidirectional"))
    )
    (net (code "88") (name "/N1_K6") (class "Default")
      (node (ref "T17") (pin "3") (pinfunction "C_3") (pintype "passive"))
      (node (ref "U$4") (pin "P7") (pinfunction "6_P7") (pintype "bidirectional"))
    )
    (net (code "89") (name "/N1_K7") (class "Default")
      (node (ref "T18") (pin "3") (pinfunction "C_3") (pintype "passive"))
      (node (ref "U$4") (pin "P6") (pinfunction "7_P6") (pintype "bidirectional"))
    )
    (net (code "90") (name "/N1_K8") (class "Default")
      (node (ref "T19") (pin "3") (pinfunction "C_3") (pintype "passive"))
      (node (ref "U$4") (pin "P5") (pinfunction "8_P5") (pintype "bidirectional"))
    )
    (net (code "91") (name "/N1_K9") (class "Default")
      (node (ref "T10") (pin "3") (pinfunction "C_3") (pintype "passive"))
      (node (ref "U$4") (pin "P4") (pinfunction "9_P4") (pintype "bidirectional"))
    )
    (net (code "92") (name "/N2_B0") (class "Default")
      (node (ref "RN30") (pin "8") (pinfunction "8_8") (pintype "passive"))
      (node (ref "T21") (pin "1") (pinfunction "B_1") (pintype "passive"))
    )
    (net (code "93") (name "/N2_B1") (class "Default")
      (node (ref "RN20") (pin "7") (pinfunction "7_7") (pintype "passive"))
      (node (ref "T22") (pin "1") (pinfunction "B_1") (pintype "passive"))
    )
    (net (code "94") (name "/N2_B2") (class "Default")
      (node (ref "RN20") (pin "8") (pinfunction "8_8") (pintype "passive"))
      (node (ref "T23") (pin "1") (pinfunction "B_1") (pintype "passive"))
    )
    (net (code "95") (name "/N2_B3") (class "Default")
      (node (ref "RN21") (pin "5") (pinfunction "5_5") (pintype "passive"))
      (node (ref "T26") (pin "1") (pinfunction "B_1") (pintype "passive"))
    )
    (net (code "96") (name "/N2_B4") (class "Default")
      (node (ref "RN21") (pin "6") (pinfunction "6_6") (pintype "passive"))
      (node (ref "T24") (pin "1") (pinfunction "B_1") (pintype "passive"))
    )
    (net (code "97") (name "/N2_B5") (class "Default")
      (node (ref "RN21") (pin "7") (pinfunction "7_7") (pintype "passive"))
      (node (ref "T25") (pin "1") (pinfunction "B_1") (pintype "passive"))
    )
    (net (code "98") (name "/N2_B6") (class "Default")
      (node (ref "RN21") (pin "8") (pinfunction "8_8") (pintype "passive"))
      (node (ref "T27") (pin "1") (pinfunction "B_1") (pintype "passive"))
    )
    (net (code "99") (name "/N2_B7") (class "Default")
      (node (ref "RN30") (pin "5") (pinfunction "5_5") (pintype "passive"))
      (node (ref "T28") (pin "1") (pinfunction "B_1") (pintype "passive"))
    )
    (net (code "100") (name "/N2_B8") (class "Default")
      (node (ref "RN30") (pin "6") (pinfunction "6_6") (pintype "passive"))
      (node (ref "T29") (pin "1") (pinfunction "B_1") (pintype "passive"))
    )
    (net (code "101") (name "/N2_B9") (class "Default")
      (node (ref "RN30") (pin "7") (pinfunction "7_7") (pintype "passive"))
      (node (ref "T20") (pin "1") (pinfunction "B_1") (pintype "passive"))
    )
    (net (code "102") (name "/N2_K0") (class "Default")
      (node (ref "T21") (pin "3") (pinfunction "C_3") (pintype "passive"))
      (node (ref "U$5") (pin "P3") (pinfunction "0_P3") (pintype "bidirectional"))
    )
    (net (code "103") (name "/N2_K1") (class "Default")
      (node (ref "T22") (pin "3") (pinfunction "C_3") (pintype "passive"))
      (node (ref "U$5") (pin "P13") (pinfunction "1_P13") (pintype "bidirectional"))
    )
    (net (code "104") (name "/N2_K2") (class "Default")
      (node (ref "T23") (pin "3") (pinfunction "C_3") (pintype "passive"))
      (node (ref "U$5") (pin "P12") (pinfunction "2_P12") (pintype "bidirectional"))
    )
    (net (code "105") (name "/N2_K3") (class "Default")
      (node (ref "T26") (pin "3") (pinfunction "C_3") (pintype "passive"))
      (node (ref "U$5") (pin "P11") (pinfunction "3_P11") (pintype "bidirectional"))
    )
    (net (code "106") (name "/N2_K4") (class "Default")
      (node (ref "T24") (pin "3") (pinfunction "C_3") (pintype "passive"))
      (node (ref "U$5") (pin "P10") (pinfunction "4_P10") (pintype "bidirectional"))
    )
    (net (code "107") (name "/N2_K5") (class "Default")
      (node (ref "T25") (pin "3") (pinfunction "C_3") (pintype "passive"))
      (node (ref "U$5") (pin "P9") (pinfunction "5_P9") (pintype "bidirectional"))
    )
    (net (code "108") (name "/N2_K6") (class "Default")
      (node (ref "T27") (pin "3") (pinfunction "C_3") (pintype "passive"))
      (node (ref "U$5") (pin "P7") (pinfunction "6_P7") (pintype "bidirectional"))
    )
    (net (code "109") (name "/N2_K7") (class "Default")
      (node (ref "T28") (pin "3") (pinfunction "C_3") (pintype "passive"))
      (node (ref "U$5") (pin "P6") (pinfunction "7_P6") (pintype "bidirectional"))
    )
    (net (code "110") (name "/N2_K8") (class "Default")
      (node (ref "T29") (pin "3") (pinfunction "C_3") (pintype "passive"))
      (node (ref "U$5") (pin "P5") (pinfunction "8_P5") (pintype "bidirectional"))
    )
    (net (code "111") (name "/N2_K9") (class "Default")
      (node (ref "T20") (pin "3") (pinfunction "C_3") (pintype "passive"))
      (node (ref "U$5") (pin "P4") (pinfunction "9_P4") (pintype "bidirectional"))
    )
    (net (code "112") (name "/N3_B0") (class "Default")
      (node (ref "RN41") (pin "8") (pinfunction "8_8") (pintype "passive"))
      (node (ref "T31") (pin "1") (pinfunction "B_1") (pintype "passive"))
    )
    (net (code "113") (name "/N3_B1") (class "Default")
      (node (ref "RN31") (pin "7") (pinfunction "7_7") (pintype "passive"))
      (node (ref "T32") (pin "1") (pinfunction "B_1") (pintype "passive"))
    )
    (net (code "114") (name "/N3_B2") (class "Default")
      (node (ref "RN31") (pin "8") (pinfunction "8_8") (pintype "passive"))
      (node (ref "T33") (pin "1") (pinfunction "B_1") (pintype "passive"))
    )
    (net (code "115") (name "/N3_B3") (class "Default")
      (node (ref "RN40") (pin "5") (pinfunction "5_5") (pintype "passive"))
      (node (ref "T36") (pin "1") (pinfunction "B_1") (pintype "passive"))
    )
    (net (code "116") (name "/N3_B4") (class "Default")
      (node (ref "RN40") (pin "6") (pinfunction "6_6") (pintype "passive"))
      (node (ref "T34") (pin "1") (pinfunction "B_1") (pintype "passive"))
    )
    (net (code "117") (name "/N3_B5") (class "Default")
      (node (ref "RN40") (pin "7") (pinfunction "7_7") (pintype "passive"))
      (node (ref "T35") (pin "1") (pinfunction "B_1") (pintype "passive"))
    )
    (net (code "118") (name "/N3_B6") (class "Default")
      (node (ref "RN40") (pin "8") (pinfunction "8_8") (pintype "passive"))
      (node (ref "T37") (pin "1") (pinfunction "B_1") (pintype "passive"))
    )
    (net (code "119") (name "/N3_B7") (class "Default")
      (node (ref "RN41") (pin "5") (pinfunction "5_5") (pintype "passive"))
      (node (ref "T38") (pin "1") (pinfunction "B_1") (pintype "passive"))
    )
    (net (code "120") (name "/N3_B8") (class "Default")
      (node (ref "RN41") (pin "6") (pinfunction "6_6") (pintype "passive"))
      (node (ref "T39") (pin "1") (pinfunction "B_1") (pintype "passive"))
    )
    (net (code "121") (name "/N3_B9") (class "Default")
      (node (ref "RN41") (pin "7") (pinfunction "7_7") (pintype "passive"))
      (node (ref "T30") (pin "1") (pinfunction "B_1") (pintype "passive"))
    )
    (net (code "122") (name "/N3_K0") (class "Default")
      (node (ref "T31") (pin "3") (pinfunction "C_3") (pintype "passive"))
      (node (ref "U$6") (pin "P3") (pinfunction "0_P3") (pintype "bidirectional"))
    )
    (net (code "123") (name "/N3_K1") (class "Default")
      (node (ref "T32") (pin "3") (pinfunction "C_3") (pintype "passive"))
      (node (ref "U$6") (pin "P13") (pinfunction "1_P13") (pintype "bidirectional"))
    )
    (net (code "124") (name "/N3_K2") (class "Default")
      (node (ref "T33") (pin "3") (pinfunction "C_3") (pintype "passive"))
      (node (ref "U$6") (pin "P12") (pinfunction "2_P12") (pintype "bidirectional"))
    )
    (net (code "125") (name "/N3_K3") (class "Default")
      (node (ref "T36") (pin "3") (pinfunction "C_3") (pintype "passive"))
      (node (ref "U$6") (pin "P11") (pinfunction "3_P11") (pintype "bidirectional"))
    )
    (net (code "126") (name "/N3_K4") (class "Default")
      (node (ref "T34") (pin "3") (pinfunction "C_3") (pintype "passive"))
      (node (ref "U$6") (pin "P10") (pinfunction "4_P10") (pintype "bidirectional"))
    )
    (net (code "127") (name "/N3_K5") (class "Default")
      (node (ref "T35") (pin "3") (pinfunction "C_3") (pintype "passive"))
      (node (ref "U$6") (pin "P9") (pinfunction "5_P9") (pintype "bidirectional"))
    )
    (net (code "128") (name "/N3_K6") (class "Default")
      (node (ref "T37") (pin "3") (pinfunction "C_3") (pintype "passive"))
      (node (ref "U$6") (pin "P7") (pinfunction "6_P7") (pintype "bidirectional"))
    )
    (net (code "129") (name "/N3_K7") (class "Default")
      (node (ref "T38") (pin "3") (pinfunction "C_3") (pintype "passive"))
      (node (ref "U$6") (pin "P6") (pinfunction "7_P6") (pintype "bidirectional"))
    )
    (net (code "130") (name "/N3_K8") (class "Default")
      (node (ref "T39") (pin "3") (pinfunction "C_3") (pintype "passive"))
      (node (ref "U$6") (pin "P5") (pinfunction "8_P5") (pintype "bidirectional"))
    )
    (net (code "131") (name "/N3_K9") (class "Default")
      (node (ref "T30") (pin "3") (pinfunction "C_3") (pintype "passive"))
      (node (ref "U$6") (pin "P4") (pinfunction "9_P4") (pintype "bidirectional"))
    )
    (net (code "132") (name "/N4_B0") (class "Default")
      (node (ref "RN60") (pin "6") (pinfunction "6_6") (pintype "passive"))
      (node (ref "T41") (pin "1") (pinfunction "B_1") (pintype "passive"))
    )
    (net (code "133") (name "/N4_B1") (class "Default")
      (node (ref "RN50") (pin "5") (pinfunction "5_5") (pintype "passive"))
      (node (ref "T42") (pin "1") (pinfunction "B_1") (pintype "passive"))
    )
    (net (code "134") (name "/N4_B2") (class "Default")
      (node (ref "RN50") (pin "6") (pinfunction "6_6") (pintype "passive"))
      (node (ref "T43") (pin "1") (pinfunction "B_1") (pintype "passive"))
    )
    (net (code "135") (name "/N4_B3") (class "Default")
      (node (ref "RN50") (pin "7") (pinfunction "7_7") (pintype "passive"))
      (node (ref "T46") (pin "1") (pinfunction "B_1") (pintype "passive"))
    )
    (net (code "136") (name "/N4_B4") (class "Default")
      (node (ref "RN50") (pin "8") (pinfunction "8_8") (pintype "passive"))
      (node (ref "T44") (pin "1") (pinfunction "B_1") (pintype "passive"))
    )
    (net (code "137") (name "/N4_B5") (class "Default")
      (node (ref "RN51") (pin "5") (pinfunction "5_5") (pintype "passive"))
      (node (ref "T45") (pin "1") (pinfunction "B_1") (pintype "passive"))
    )
    (net (code "138") (name "/N4_B6") (class "Default")
      (node (ref "RN51") (pin "6") (pinfunction "6_6") (pintype "passive"))
      (node (ref "T47") (pin "1") (pinfunction "B_1") (pintype "passive"))
    )
    (net (code "139") (name "/N4_B7") (class "Default")
      (node (ref "RN51") (pin "7") (pinfunction "7_7") (pintype "passive"))
      (node (ref "T48") (pin "1") (pinfunction "B_1") (pintype "passive"))
    )
    (net (code "140") (name "/N4_B8") (class "Default")
      (node (ref "RN51") (pin "8") (pinfunction "8_8") (pintype "passive"))
      (node (ref "T49") (pin "1") (pinfunction "B_1") (pintype "passive"))
    )
    (net (code "141") (name "/N4_B9") (class "Default")
      (node (ref "RN60") (pin "5") (pinfunction "5_5") (pintype "passive"))
      (node (ref "T40") (pin "1") (pinfunction "B_1") (pintype "passive"))
    )
    (net (code "142") (name "/N4_K0") (class "Default")
      (node (ref "T41") (pin "3") (pinfunction "C_3") (pintype "passive"))
      (node (ref "U$7") (pin "P3") (pinfunction "0_P3") (pintype "bidirectional"))
    )
    (net (code "143") (name "/N4_K1") (class "Default")
      (node (ref "T42") (pin "3") (pinfunction "C_3") (pintype "passive"))
      (node (ref "U$7") (pin "P13") (pinfunction "1_P13") (pintype "bidirectional"))
    )
    (net (code "144") (name "/N4_K2") (class "Default")
      (node (ref "T43") (pin "3") (pinfunction "C_3") (pintype "passive"))
      (node (ref "U$7") (pin "P12") (pinfunction "2_P12") (pintype "bidirectional"))
    )
    (net (code "145") (name "/N4_K3") (class "Default")
      (node (ref "T46") (pin "3") (pinfunction "C_3") (pintype "passive"))
      (node (ref "U$7") (pin "P11") (pinfunction "3_P11") (pintype "bidirectional"))
    )
    (net (code "146") (name "/N4_K4") (class "Default")
      (node (ref "T44") (pin "3") (pinfunction "C_3") (pintype "passive"))
      (node (ref "U$7") (pin "P10") (pinfunction "4_P10") (pintype "bidirectional"))
    )
    (net (code "147") (name "/N4_K5") (class "Default")
      (node (ref "T45") (pin "3") (pinfunction "C_3") (pintype "passive"))
      (node (ref "U$7") (pin "P9") (pinfunction "5_P9") (pintype "bidirectional"))
    )
    (net (code "148") (name "/N4_K6") (class "Default")
      (node (ref "T47") (pin "3") (pinfunction "C_3") (pintype "passive"))
      (node (ref "U$7") (pin "P7") (pinfunction "6_P7") (pintype "bidirectional"))
    )
    (net (code "149") (name "/N4_K7") (class "Default")
      (node (ref "T48") (pin "3") (pinfunction "C_3") (pintype "passive"))
      (node (ref "U$7") (pin "P6") (pinfunction "7_P6") (pintype "bidirectional"))
    )
    (net (code "150") (name "/N4_K8") (class "Default")
      (node (ref "T49") (pin "3") (pinfunction "C_3") (pintype "passive"))
      (node (ref "U$7") (pin "P5") (pinfunction "8_P5") (pintype "bidirectional"))
    )
    (net (code "151") (name "/N4_K9") (class "Default")
      (node (ref "T40") (pin "3") (pinfunction "C_3") (pintype "passive"))
      (node (ref "U$7") (pin "P4") (pinfunction "9_P4") (pintype "bidirectional"))
    )
    (net (code "152") (name "/N5_B0") (class "Default")
      (node (ref "RN71") (pin "6") (pinfunction "6_6") (pintype "passive"))
      (node (ref "T51") (pin "1") (pinfunction "B_1") (pintype "passive"))
    )
    (net (code "153") (name "/N5_B1") (class "Default")
      (node (ref "RN61") (pin "5") (pinfunction "5_5") (pintype "passive"))
      (node (ref "T52") (pin "1") (pinfunction "B_1") (pintype "passive"))
    )
    (net (code "154") (name "/N5_B2") (class "Default")
      (node (ref "RN61") (pin "6") (pinfunction "6_6") (pintype "passive"))
      (node (ref "T53") (pin "1") (pinfunction "B_1") (pintype "passive"))
    )
    (net (code "155") (name "/N5_B3") (class "Default")
      (node (ref "RN61") (pin "7") (pinfunction "7_7") (pintype "passive"))
      (node (ref "T56") (pin "1") (pinfunction "B_1") (pintype "passive"))
    )
    (net (code "156") (name "/N5_B4") (class "Default")
      (node (ref "RN61") (pin "8") (pinfunction "8_8") (pintype "passive"))
      (node (ref "T54") (pin "1") (pinfunction "B_1") (pintype "passive"))
    )
    (net (code "157") (name "/N5_B5") (class "Default")
      (node (ref "RN70") (pin "5") (pinfunction "5_5") (pintype "passive"))
      (node (ref "T55") (pin "1") (pinfunction "B_1") (pintype "passive"))
    )
    (net (code "158") (name "/N5_B6") (class "Default")
      (node (ref "RN70") (pin "6") (pinfunction "6_6") (pintype "passive"))
      (node (ref "T57") (pin "1") (pinfunction "B_1") (pintype "passive"))
    )
    (net (code "159") (name "/N5_B7") (class "Default")
      (node (ref "RN70") (pin "7") (pinfunction "7_7") (pintype "passive"))
      (node (ref "T58") (pin "1") (pinfunction "B_1") (pintype "passive"))
    )
    (net (code "160") (name "/N5_B8") (class "Default")
      (node (ref "RN70") (pin "8") (pinfunction "8_8") (pintype "passive"))
      (node (ref "T59") (pin "1") (pinfunction "B_1") (pintype "passive"))
    )
    (net (code "161") (name "/N5_B9") (class "Default")
      (node (ref "RN71") (pin "5") (pinfunction "5_5") (pintype "passive"))
      (node (ref "T50") (pin "1") (pinfunction "B_1") (pintype "passive"))
    )
    (net (code "162") (name "/N5_K0") (class "Default")
      (node (ref "T51") (pin "3") (pinfunction "C_3") (pintype "passive"))
      (node (ref "U$8") (pin "P3") (pinfunction "0_P3") (pintype "bidirectional"))
    )
    (net (code "163") (name "/N5_K1") (class "Default")
      (node (ref "T52") (pin "3") (pinfunction "C_3") (pintype "passive"))
      (node (ref "U$8") (pin "P13") (pinfunction "1_P13") (pintype "bidirectional"))
    )
    (net (code "164") (name "/N5_K2") (class "Default")
      (node (ref "T53") (pin "3") (pinfunction "C_3") (pintype "passive"))
      (node (ref "U$8") (pin "P12") (pinfunction "2_P12") (pintype "bidirectional"))
    )
    (net (code "165") (name "/N5_K3") (class "Default")
      (node (ref "T56") (pin "3") (pinfunction "C_3") (pintype "passive"))
      (node (ref "U$8") (pin "P11") (pinfunction "3_P11") (pintype "bidirectional"))
    )
    (net (code "166") (name "/N5_K4") (class "Default")
      (node (ref "T54") (pin "3") (pinfunction "C_3") (pintype "passive"))
      (node (ref "U$8") (pin "P10") (pinfunction "4_P10") (pintype "bidirectional"))
    )
    (net (code "167") (name "/N5_K5") (class "Default")
      (node (ref "T55") (pin "3") (pinfunction "C_3") (pintype "passive"))
      (node (ref "U$8") (pin "P9") (pinfunction "5_P9") (pintype "bidirectional"))
    )
    (net (code "168") (name "/N5_K6") (class "Default")
      (node (ref "T57") (pin "3") (pinfunction "C_3") (pintype "passive"))
      (node (ref "U$8") (pin "P7") (pinfunction "6_P7") (pintype "bidirectional"))
    )
    (net (code "169") (name "/N5_K7") (class "Default")
      (node (ref "T58") (pin "3") (pinfunction "C_3") (pintype "passive"))
      (node (ref "U$8") (pin "P6") (pinfunction "7_P6") (pintype "bidirectional"))
    )
    (net (code "170") (name "/N5_K8") (class "Default")
      (node (ref "T59") (pin "3") (pinfunction "C_3") (pintype "passive"))
      (node (ref "U$8") (pin "P5") (pinfunction "8_P5") (pintype "bidirectional"))
    )
    (net (code "171") (name "/N5_K9") (class "Default")
      (node (ref "T50") (pin "3") (pinfunction "C_3") (pintype "passive"))
      (node (ref "U$8") (pin "P4") (pinfunction "9_P4") (pintype "bidirectional"))
    )
    (net (code "172") (name "/N6_B0") (class "Default")
      (node (ref "RN81") (pin "8") (pinfunction "8_8") (pintype "passive"))
      (node (ref "T61") (pin "1") (pinfunction "B_1") (pintype "passive"))
    )
    (net (code "173") (name "/N6_B1") (class "Default")
      (node (ref "RN71") (pin "7") (pinfunction "7_7") (pintype "passive"))
      (node (ref "T62") (pin "1") (pinfunction "B_1") (pintype "passive"))
    )
    (net (code "174") (name "/N6_B2") (class "Default")
      (node (ref "RN71") (pin "8") (pinfunction "8_8") (pintype "passive"))
      (node (ref "T63") (pin "1") (pinfunction "B_1") (pintype "passive"))
    )
    (net (code "175") (name "/N6_B3") (class "Default")
      (node (ref "RN80") (pin "5") (pinfunction "5_5") (pintype "passive"))
      (node (ref "T66") (pin "1") (pinfunction "B_1") (pintype "passive"))
    )
    (net (code "176") (name "/N6_B4") (class "Default")
      (node (ref "RN80") (pin "6") (pinfunction "6_6") (pintype "passive"))
      (node (ref "T64") (pin "1") (pinfunction "B_1") (pintype "passive"))
    )
    (net (code "177") (name "/N6_B5") (class "Default")
      (node (ref "RN80") (pin "7") (pinfunction "7_7") (pintype "passive"))
      (node (ref "T65") (pin "1") (pinfunction "B_1") (pintype "passive"))
    )
    (net (code "178") (name "/N6_B6") (class "Default")
      (node (ref "RN80") (pin "8") (pinfunction "8_8") (pintype "passive"))
      (node (ref "T67") (pin "1") (pinfunction "B_1") (pintype "passive"))
    )
    (net (code "179") (name "/N6_B7") (class "Default")
      (node (ref "RN81") (pin "5") (pinfunction "5_5") (pintype "passive"))
      (node (ref "T68") (pin "1") (pinfunction "B_1") (pintype "passive"))
    )
    (net (code "180") (name "/N6_B8") (class "Default")
      (node (ref "RN81") (pin "6") (pinfunction "6_6") (pintype "passive"))
      (node (ref "T69") (pin "1") (pinfunction "B_1") (pintype "passive"))
    )
    (net (code "181") (name "/N6_B9") (class "Default")
      (node (ref "RN81") (pin "7") (pinfunction "7_7") (pintype "passive"))
      (node (ref "T60") (pin "1") (pinfunction "B_1") (pintype "passive"))
    )
    (net (code "182") (name "/N6_K0") (class "Default")
      (node (ref "T61") (pin "3") (pinfunction "C_3") (pintype "passive"))
      (node (ref "U$9") (pin "P3") (pinfunction "0_P3") (pintype "bidirectional"))
    )
    (net (code "183") (name "/N6_K1") (class "Default")
      (node (ref "T62") (pin "3") (pinfunction "C_3") (pintype "passive"))
      (node (ref "U$9") (pin "P13") (pinfunction "1_P13") (pintype "bidirectional"))
    )
    (net (code "184") (name "/N6_K2") (class "Default")
      (node (ref "T63") (pin "3") (pinfunction "C_3") (pintype "passive"))
      (node (ref "U$9") (pin "P12") (pinfunction "2_P12") (pintype "bidirectional"))
    )
    (net (code "185") (name "/N6_K3") (class "Default")
      (node (ref "T66") (pin "3") (pinfunction "C_3") (pintype "passive"))
      (node (ref "U$9") (pin "P11") (pinfunction "3_P11") (pintype "bidirectional"))
    )
    (net (code "186") (name "/N6_K4") (class "Default")
      (node (ref "T64") (pin "3") (pinfunction "C_3") (pintype "passive"))
      (node (ref "U$9") (pin "P10") (pinfunction "4_P10") (pintype "bidirectional"))
    )
    (net (code "187") (name "/N6_K5") (class "Default")
      (node (ref "T65") (pin "3") (pinfunction "C_3") (pintype "passive"))
      (node (ref "U$9") (pin "P9") (pinfunction "5_P9") (pintype "bidirectional"))
    )
    (net (code "188") (name "/N6_K6") (class "Default")
      (node (ref "T67") (pin "3") (pinfunction "C_3") (pintype "passive"))
      (node (ref "U$9") (pin "P7") (pinfunction "6_P7") (pintype "bidirectional"))
    )
    (net (code "189") (name "/N6_K7") (class "Default")
      (node (ref "T68") (pin "3") (pinfunction "C_3") (pintype "passive"))
      (node (ref "U$9") (pin "P6") (pinfunction "7_P6") (pintype "bidirectional"))
    )
    (net (code "190") (name "/N6_K8") (class "Default")
      (node (ref "T69") (pin "3") (pinfunction "C_3") (pintype "passive"))
      (node (ref "U$9") (pin "P5") (pinfunction "8_P5") (pintype "bidirectional"))
    )
    (net (code "191") (name "/N6_K9") (class "Default")
      (node (ref "T60") (pin "3") (pinfunction "C_3") (pintype "passive"))
      (node (ref "U$9") (pin "P4") (pinfunction "9_P4") (pintype "bidirectional"))
    )
    (net (code "192") (name "/RCK") (class "Default")
      (node (ref "IC1") (pin "12") (pinfunction "RCK_12") (pintype "input"))
      (node (ref "IC2") (pin "12") (pinfunction "RCK_12") (pintype "input"))
      (node (ref "IC3") (pin "12") (pinfunction "RCK_12") (pintype "input"))
      (node (ref "IC4") (pin "12") (pinfunction "RCK_12") (pintype "input"))
      (node (ref "IC5") (pin "12") (pinfunction "RCK_12") (pintype "input"))
      (node (ref "IC6") (pin "12") (pinfunction "RCK_12") (pintype "input"))
      (node (ref "IC7") (pin "12") (pinfunction "RCK_12") (pintype "input"))
      (node (ref "IC8") (pin "12") (pinfunction "RCK_12") (pintype "input"))
      (node (ref "JP1") (pin "5") (pinfunction "5_5") (pintype "passive"))
    )
    (net (code "193") (name "/SCK") (class "Default")
      (node (ref "IC1") (pin "11") (pinfunction "SCK_11") (pintype "input"))
      (node (ref "IC2") (pin "11") (pinfunction "SCK_11") (pintype "input"))
      (node (ref "IC3") (pin "11") (pinfunction "SCK_11") (pintype "input"))
      (node (ref "IC4") (pin "11") (pinfunction "SCK_11") (pintype "input"))
      (node (ref "IC5") (pin "11") (pinfunction "SCK_11") (pintype "input"))
      (node (ref "IC6") (pin "11") (pinfunction "SCK_11") (pintype "input"))
      (node (ref "IC7") (pin "11") (pinfunction "SCK_11") (pintype "input"))
      (node (ref "IC8") (pin "11") (pinfunction "SCK_11") (pintype "input"))
      (node (ref "JP1") (pin "3") (pinfunction "3_3") (pintype "passive"))
    )
    (net (code "194") (name "/SCL") (class "Default")
      (node (ref "IC1") (pin "10") (pinfunction "SCL_10") (pintype "input"))
      (node (ref "IC2") (pin "10") (pinfunction "SCL_10") (pintype "input"))
      (node (ref "IC3") (pin "10") (pinfunction "SCL_10") (pintype "input"))
      (node (ref "IC4") (pin "10") (pinfunction "SCL_10") (pintype "input"))
      (node (ref "IC5") (pin "10") (pinfunction "SCL_10") (pintype "input"))
      (node (ref "IC6") (pin "10") (pinfunction "SCL_10") (pintype "input"))
      (node (ref "IC7") (pin "10") (pinfunction "SCL_10") (pintype "input"))
      (node (ref "IC8") (pin "10") (pinfunction "SCL_10") (pintype "input"))
      (node (ref "JP1") (pin "2") (pinfunction "2_2") (pintype "passive"))
    )
    (net (code "195") (name "GND") (class "Default")
      (node (ref "C1") (pin "2") (pinfunction "2_2") (pintype "passive"))
      (node (ref "C2") (pin "2") (pinfunction "2_2") (pintype "passive"))
      (node (ref "C3") (pin "2") (pinfunction "2_2") (pintype "passive"))
      (node (ref "C4") (pin "2") (pinfunction "2_2") (pintype "passive"))
      (node (ref "C5") (pin "2") (pinfunction "2_2") (pintype "passive"))
      (node (ref "C6") (pin "2") (pinfunction "2_2") (pintype "passive"))
      (node (ref "C7") (pin "2") (pinfunction "2_2") (pintype "passive"))
      (node (ref "C8") (pin "2") (pinfunction "2_2") (pintype "passive"))
      (node (ref "IC1") (pin "8") (pinfunction "GND_8") (pintype "power_in"))
      (node (ref "IC2") (pin "8") (pinfunction "GND_8") (pintype "power_in"))
      (node (ref "IC3") (pin "8") (pinfunction "GND_8") (pintype "power_in"))
      (node (ref "IC4") (pin "8") (pinfunction "GND_8") (pintype "power_in"))
      (node (ref "IC5") (pin "8") (pinfunction "GND_8") (pintype "power_in"))
      (node (ref "IC6") (pin "8") (pinfunction "GND_8") (pintype "power_in"))
      (node (ref "IC7") (pin "8") (pinfunction "GND_8") (pintype "power_in"))
      (node (ref "IC8") (pin "8") (pinfunction "GND_8") (pintype "power_in"))
      (node (ref "JP1") (pin "6") (pinfunction "6_6") (pintype "passive"))
      (node (ref "JP2") (pin "2") (pinfunction "2_2") (pintype "passive"))
      (node (ref "JP2") (pin "3") (pinfunction "3_3") (pintype "passive"))
      (node (ref "JP2") (pin "4") (pinfunction "4_4") (pintype "passive"))
      (node (ref "JP2") (pin "5") (pinfunction "5_5") (pintype "passive"))
      (node (ref "T1") (pin "2") (pinfunction "E_2") (pintype "passive"))
      (node (ref "T10") (pin "2") (pinfunction "E_2") (pintype "passive"))
      (node (ref "T11") (pin "2") (pinfunction "E_2") (pintype "passive"))
      (node (ref "T12") (pin "2") (pinfunction "E_2") (pintype "passive"))
      (node (ref "T13") (pin "2") (pinfunction "E_2") (pintype "passive"))
      (node (ref "T14") (pin "2") (pinfunction "E_2") (pintype "passive"))
      (node (ref "T15") (pin "2") (pinfunction "E_2") (pintype "passive"))
      (node (ref "T16") (pin "2") (pinfunction "E_2") (pintype "passive"))
      (node (ref "T17") (pin "2") (pinfunction "E_2") (pintype "passive"))
      (node (ref "T18") (pin "2") (pinfunction "E_2") (pintype "passive"))
      (node (ref "T19") (pin "2") (pinfunction "E_2") (pintype "passive"))
      (node (ref "T2") (pin "2") (pinfunction "E_2") (pintype "passive"))
      (node (ref "T20") (pin "2") (pinfunction "E_2") (pintype "passive"))
      (node (ref "T21") (pin "2") (pinfunction "E_2") (pintype "passive"))
      (node (ref "T22") (pin "2") (pinfunction "E_2") (pintype "passive"))
      (node (ref "T23") (pin "2") (pinfunction "E_2") (pintype "passive"))
      (node (ref "T24") (pin "2") (pinfunction "E_2") (pintype "passive"))
      (node (ref "T25") (pin "2") (pinfunction "E_2") (pintype "passive"))
      (node (ref "T26") (pin "2") (pinfunction "E_2") (pintype "passive"))
      (node (ref "T27") (pin "2") (pinfunction "E_2") (pintype "passive"))
      (node (ref "T28") (pin "2") (pinfunction "E_2") (pintype "passive"))
      (node (ref "T29") (pin "2") (pinfunction "E_2") (pintype "passive"))
      (node (ref "T3") (pin "2") (pinfunction "E_2") (pintype "passive"))
      (node (ref "T30") (pin "2") (pinfunction "E_2") (pintype "passive"))
      (node (ref "T31") (pin "2") (pinfunction "E_2") (pintype "passive"))
      (node (ref "T32") (pin "2") (pinfunction "E_2") (pintype "passive"))
      (node (ref "T33") (pin "2") (pinfunction "E_2") (pintype "passive"))
      (node (ref "T34") (pin "2") (pinfunction "E_2") (pintype "passive"))
      (node (ref "T35") (pin "2") (pinfunction "E_2") (pintype "passive"))
      (node (ref "T36") (pin "2") (pinfunction "E_2") (pintype "passive"))
      (node (ref "T37") (pin "2") (pinfunction "E_2") (pintype "passive"))
      (node (ref "T38") (pin "2") (pinfunction "E_2") (pintype "passive"))
      (node (ref "T39") (pin "2") (pinfunction "E_2") (pintype "passive"))
      (node (ref "T4") (pin "2") (pinfunction "E_2") (pintype "passive"))
      (node (ref "T40") (pin "2") (pinfunction "E_2") (pintype "passive"))
      (node (ref "T41") (pin "2") (pinfunction "E_2") (pintype "passive"))
      (node (ref "T42") (pin "2") (pinfunction "E_2") (pintype "passive"))
      (node (ref "T43") (pin "2") (pinfunction "E_2") (pintype "passive"))
      (node (ref "T44") (pin "2") (pinfunction "E_2") (pintype "passive"))
      (node (ref "T45") (pin "2") (pinfunction "E_2") (pintype "passive"))
      (node (ref "T46") (pin "2") (pinfunction "E_2") (pintype "passive"))
      (node (ref "T47") (pin "2") (pinfunction "E_2") (pintype "passive"))
      (node (ref "T48") (pin "2") (pinfunction "E_2") (pintype "passive"))
      (node (ref "T49") (pin "2") (pinfunction "E_2") (pintype "passive"))
      (node (ref "T50") (pin "2") (pinfunction "E_2") (pintype "passive"))
      (node (ref "T51") (pin "2") (pinfunction "E_2") (pintype "passive"))
      (node (ref "T52") (pin "2") (pinfunction "E_2") (pintype "passive"))
      (node (ref "T53") (pin "2") (pinfunction "E_2") (pintype "passive"))
      (node (ref "T54") (pin "2") (pinfunction "E_2") (pintype "passive"))
      (node (ref "T55") (pin "2") (pinfunction "E_2") (pintype "passive"))
      (node (ref "T56") (pin "2") (pinfunction "E_2") (pintype "passive"))
      (node (ref "T57") (pin "2") (pinfunction "E_2") (pintype "passive"))
      (node (ref "T58") (pin "2") (pinfunction "E_2") (pintype "passive"))
      (node (ref "T59") (pin "2") (pinfunction "E_2") (pintype "passive"))
      (node (ref "T60") (pin "2") (pinfunction "E_2") (pintype "passive"))
      (node (ref "T61") (pin "2") (pinfunction "E_2") (pintype "passive"))
      (node (ref "T62") (pin "2") (pinfunction "E_2") (pintype "passive"))
      (node (ref "T63") (pin "2") (pinfunction "E_2") (pintype "passive"))
      (node (ref "T64") (pin "2") (pinfunction "E_2") (pintype "passive"))
      (node (ref "T65") (pin "2") (pinfunction "E_2") (pintype "passive"))
      (node (ref "T66") (pin "2") (pinfunction "E_2") (pintype "passive"))
      (node (ref "T67") (pin "2") (pinfunction "E_2") (pintype "passive"))
      (node (ref "T68") (pin "2") (pinfunction "E_2") (pintype "passive"))
      (node (ref "T69") (pin "2") (pinfunction "E_2") (pintype "passive"))
    )
    (net (code "196") (name "Net-(GL1-A)") (class "Default")
      (node (ref "GL1") (pin "1") (pinfunction "A_1") (pintype "passive"))
      (node (ref "R1") (pin "1") (pinfunction "1_1") (pintype "passive"))
    )
    (net (code "197") (name "Net-(GL1-A1)") (class "Default")
      (node (ref "GL1") (pin "2") (pinfunction "A1_2") (pintype "passive"))
      (node (ref "T1") (pin "3") (pinfunction "C_3") (pintype "passive"))
    )
    (net (code "198") (name "Net-(GL2-A)") (class "Default")
      (node (ref "GL2") (pin "1") (pinfunction "A_1") (pintype "passive"))
      (node (ref "R2") (pin "1") (pinfunction "1_1") (pintype "passive"))
    )
    (net (code "199") (name "Net-(GL2-A1)") (class "Default")
      (node (ref "GL2") (pin "2") (pinfunction "A1_2") (pintype "passive"))
      (node (ref "T2") (pin "3") (pinfunction "C_3") (pintype "passive"))
    )
    (net (code "200") (name "Net-(GL3-A)") (class "Default")
      (node (ref "GL3") (pin "1") (pinfunction "A_1") (pintype "passive"))
      (node (ref "R3") (pin "1") (pinfunction "1_1") (pintype "passive"))
    )
    (net (code "201") (name "Net-(GL3-A1)") (class "Default")
      (node (ref "GL3") (pin "2") (pinfunction "A1_2") (pintype "passive"))
      (node (ref "T3") (pin "3") (pinfunction "C_3") (pintype "passive"))
    )
    (net (code "202") (name "Net-(GL4-A)") (class "Default")
      (node (ref "GL4") (pin "1") (pinfunction "A_1") (pintype "passive"))
      (node (ref "R4") (pin "1") (pinfunction "1_1") (pintype "passive"))
    )
    (net (code "203") (name "Net-(GL4-A1)") (class "Default")
      (node (ref "GL4") (pin "2") (pinfunction "A1_2") (pintype "passive"))
      (node (ref "T4") (pin "3") (pinfunction "C_3") (pintype "passive"))
    )
    (net (code "204") (name "Net-(IC1A-QH*)") (class "Default")
      (node (ref "IC1") (pin "9") (pinfunction "QH*_9") (pintype "tri_state"))
      (node (ref "IC2") (pin "14") (pinfunction "SER_14") (pintype "input"))
    )
    (net (code "205") (name "Net-(IC2A-QH*)") (class "Default")
      (node (ref "IC2") (pin "9") (pinfunction "QH*_9") (pintype "tri_state"))
      (node (ref "IC3") (pin "14") (pinfunction "SER_14") (pintype "input"))
    )
    (net (code "206") (name "Net-(IC3A-QH*)") (class "Default")
      (node (ref "IC3") (pin "9") (pinfunction "QH*_9") (pintype "tri_state"))
      (node (ref "IC4") (pin "14") (pinfunction "SER_14") (pintype "input"))
    )
    (net (code "207") (name "Net-(IC4A-QH*)") (class "Default")
      (node (ref "IC4") (pin "9") (pinfunction "QH*_9") (pintype "tri_state"))
      (node (ref "IC5") (pin "14") (pinfunction "SER_14") (pintype "input"))
    )
    (net (code "208") (name "Net-(IC5A-QH*)") (class "Default")
      (node (ref "IC5") (pin "9") (pinfunction "QH*_9") (pintype "tri_state"))
      (node (ref "IC6") (pin "14") (pinfunction "SER_14") (pintype "input"))
    )
    (net (code "209") (name "Net-(IC6A-QH*)") (class "Default")
      (node (ref "IC6") (pin "9") (pinfunction "QH*_9") (pintype "tri_state"))
      (node (ref "IC7") (pin "14") (pinfunction "SER_14") (pintype "input"))
    )
    (net (code "210") (name "Net-(IC7A-QH*)") (class "Default")
      (node (ref "IC7") (pin "9") (pinfunction "QH*_9") (pintype "tri_state"))
      (node (ref "IC8") (pin "14") (pinfunction "SER_14") (pintype "input"))
    )
    (net (code "211") (name "Net-(U$4-A)") (class "Default")
      (node (ref "R10") (pin "1") (pinfunction "1_1") (pintype "passive"))
      (node (ref "U$4") (pin "P2") (pinfunction "A_P2") (pintype "bidirectional"))
    )
    (net (code "212") (name "Net-(U$5-A)") (class "Default")
      (node (ref "R20") (pin "1") (pinfunction "1_1") (pintype "passive"))
      (node (ref "U$5") (pin "P2") (pinfunction "A_P2") (pintype "bidirectional"))
    )
    (net (code "213") (name "Net-(U$6-A)") (class "Default")
      (node (ref "R30") (pin "1") (pinfunction "1_1") (pintype "passive"))
      (node (ref "U$6") (pin "P2") (pinfunction "A_P2") (pintype "bidirectional"))
    )
    (net (code "214") (name "Net-(U$7-A)") (class "Default")
      (node (ref "R40") (pin "1") (pinfunction "1_1") (pintype "passive"))
      (node (ref "U$7") (pin "P2") (pinfunction "A_P2") (pintype "bidirectional"))
    )
    (net (code "215") (name "Net-(U$8-A)") (class "Default")
      (node (ref "R50") (pin "1") (pinfunction "1_1") (pintype "passive"))
      (node (ref "U$8") (pin "P2") (pinfunction "A_P2") (pintype "bidirectional"))
    )
    (net (code "216") (name "Net-(U$9-A)") (class "Default")
      (node (ref "R60") (pin "1") (pinfunction "1_1") (pintype "passive"))
      (node (ref "U$9") (pin "P2") (pinfunction "A_P2") (pintype "bidirectional"))
    )
    (net (code "217") (name "VDD") (class "Default")
      (node (ref "JP2") (pin "1") (pinfunction "1_1") (pintype "passive"))
      (node (ref "R1") (pin "2") (pinfunction "2_2") (pintype "passive"))
      (node (ref "R10") (pin "2") (pinfunction "2_2") (pintype "passive"))
      (node (ref "R2") (pin "2") (pinfunction "2_2") (pintype "passive"))
      (node (ref "R20") (pin "2") (pinfunction "2_2") (pintype "passive"))
      (node (ref "R3") (pin "2") (pinfunction "2_2") (pintype "passive"))
      (node (ref "R30") (pin "2") (pinfunction "2_2") (pintype "passive"))
      (node (ref "R4") (pin "2") (pinfunction "2_2") (pintype "passive"))
      (node (ref "R40") (pin "2") (pinfunction "2_2") (pintype "passive"))
      (node (ref "R50") (pin "2") (pinfunction "2_2") (pintype "passive"))
      (node (ref "R60") (pin "2") (pinfunction "2_2") (pintype "passive"))
    )
    (net (code "218") (name "unconnected-(IC8A-QH*-Pad9)") (class "Default")
      (node (ref "IC8") (pin "9") (pinfunction "QH*_9") (pintype "tri_state"))
    )
    (net (code "219") (name "unconnected-(U$4-NC1-PadP1)") (class "Default")
      (node (ref "U$4") (pin "P1") (pinfunction "NC1_P1") (pintype "bidirectional"))
    )
    (net (code "220") (name "unconnected-(U$4-NC2-PadP8)") (class "Default")
      (node (ref "U$4") (pin "P8") (pinfunction "NC2_P8") (pintype "bidirectional"))
    )
    (net (code "221") (name "unconnected-(U$5-NC1-PadP1)") (class "Default")
      (node (ref "U$5") (pin "P1") (pinfunction "NC1_P1") (pintype "bidirectional"))
    )
    (net (code "222") (name "unconnected-(U$5-NC2-PadP8)") (class "Default")
      (node (ref "U$5") (pin "P8") (pinfunction "NC2_P8") (pintype "bidirectional"))
    )
    (net (code "223") (name "unconnected-(U$6-NC1-PadP1)") (class "Default")
      (node (ref "U$6") (pin "P1") (pinfunction "NC1_P1") (pintype "bidirectional"))
    )
    (net (code "224") (name "unconnected-(U$6-NC2-PadP8)") (class "Default")
      (node (ref "U$6") (pin "P8") (pinfunction "NC2_P8") (pintype "bidirectional"))
    )
    (net (code "225") (name "unconnected-(U$7-NC1-PadP1)") (class "Default")
      (node (ref "U$7") (pin "P1") (pinfunction "NC1_P1") (pintype "bidirectional"))
    )
    (net (code "226") (name "unconnected-(U$7-NC2-PadP8)") (class "Default")
      (node (ref "U$7") (pin "P8") (pinfunction "NC2_P8") (pintype "bidirectional"))
    )
    (net (code "227") (name "unconnected-(U$8-NC1-PadP1)") (class "Default")
      (node (ref "U$8") (pin "P1") (pinfunction "NC1_P1") (pintype "bidirectional"))
    )
    (net (code "228") (name "unconnected-(U$8-NC2-PadP8)") (class "Default")
      (node (ref "U$8") (pin "P8") (pinfunction "NC2_P8") (pintype "bidirectional"))
    )
    (net (code "229") (name "unconnected-(U$9-NC1-PadP1)") (class "Default")
      (node (ref "U$9") (pin "P1") (pinfunction "NC1_P1") (pintype "bidirectional"))
    )
    (net (code "230") (name "unconnected-(U$9-NC2-PadP8)") (class "Default")
      (node (ref "U$9") (pin "P8") (pinfunction "NC2_P8") (pintype "bidirectional"))
    )
  )
)
